# E32_Lora_T20S868MHz.net
KiCad netlist of a schematic drawn in Altium Designer
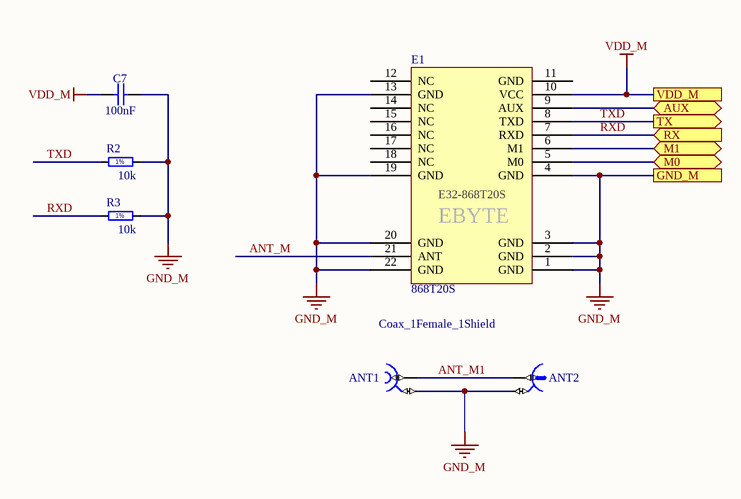
[diagram p0: E32_Lora_T20S868MHz.SchDoc]

(export (version "E")
  (design (tool "Eeschema 10.0.6"))
  (components
    (comp (ref "ANT1")
      (value "Coax_1Female_1Shield")
      (footprint "HUBER-SUHNER_85 SMA-50-0-101/111 NE")
      (fields
        (field (name "PART NUMBER") "HUBER-SUHNER_85_SMA-50-0-101/111_NE")
        (field (name "MANUFACTURER") "HUBER+SUHNER")
        (field (name "MANUFACTURER PART NUMBER") "85_SMA-50-0-101/111_NE")
        (field (name "AUTHOR") "CERN DEM JLC")
      )
      (libsource (lib "Connectors") (part "Coax_1Female_1Shield"))
    )
    (comp (ref "ANT2")
      (value "U.FL")
      (footprint "HIROSE_U.FL-R-SMT-1(10)")
      (fields
        (field (name "PART NUMBER") "HIROSE_U.FL-R-SMT-1(10)")
        (field (name "MANUFACTURER") "HIROSE (HRS)")
        (field (name "MANUFACTURER PART NUMBER") "U.FL-R-SMT-1(10)")
        (field (name "AUTHOR") "CERN DEM JLC")
      )
      (libsource (lib "Connectors") (part "Coax_1Male_1Shield"))
    )
    (comp (ref "C7")
      (value "100nF")
      (footprint "CAPC1608X87N")
      (description "Non-polarised capacitor")
      (fields
        (field (name "PART NUMBER") "CC0603_100NF_50V_10%_X7R")
        (field (name "VOLTAGE") "50V")
        (field (name "AUTHOR") "CERN DEM JLC")
      )
      (libsource (lib "Capacitors") (part "Capacitor - non polarized"))
    )
    (comp (ref "E1")
      (value "868T20S")
      (footprint "E32-T20S")
      (description "Lora Ebyte E32-T30S Module")
      (libsource (lib "alib_pnphien") (part "E32-868T20S"))
    )
    (comp (ref "R2")
      (value "10k")
      (footprint "RESC1608X55N")
      (description "Resistor - 1%")
      (fields
        (field (name "PART NUMBER") "R0603_10K_1%_0.1W_100PPM")
        (field (name "POWER") "0.1W")
        (field (name "AUTHOR") "CERN DEM JLC")
      )
      (libsource (lib "Resistors") (part "Resistor - 1%"))
    )
    (comp (ref "R3")
      (value "10k")
      (footprint "RESC1608X55N")
      (description "Resistor - 1%")
      (fields
        (field (name "PART NUMBER") "R0603_10K_1%_0.1W_100PPM")
        (field (name "POWER") "0.1W")
        (field (name "AUTHOR") "CERN DEM JLC")
      )
      (libsource (lib "Resistors") (part "Resistor - 1%"))
    )
  )
  (nets
    (net (code "1") (name "/ANT_M") (class "Default")
      (node (ref "E1") (pin "21") (pinfunction "ANT_21") (pintype "passive"))
    )
    (net (code "2") (name "/ANT_M1") (class "Default")
      (node (ref "ANT1") (pin "1") (pinfunction "1_1") (pintype "bidirectional"))
      (node (ref "ANT2") (pin "1") (pinfunction "1_1") (pintype "bidirectional"))
    )
    (net (code "3") (name "/AUX") (class "Default")
      (node (ref "E1") (pin "9") (pinfunction "AUX_9") (pintype "passive"))
    )
    (net (code "4") (name "/M0") (class "Default")
      (node (ref "E1") (pin "5") (pinfunction "M0_5") (pintype "passive"))
    )
    (net (code "5") (name "/M1") (class "Default")
      (node (ref "E1") (pin "6") (pinfunction "M1_6") (pintype "passive"))
    )
    (net (code "6") (name "/RXD") (class "Default")
      (node (ref "E1") (pin "7") (pinfunction "RXD_7") (pintype "passive"))
      (node (ref "R3") (pin "1") (pinfunction "1_1") (pintype "passive"))
    )
    (net (code "7") (name "/TXD") (class "Default")
      (node (ref "E1") (pin "8") (pinfunction "TXD_8") (pintype "passive"))
      (node (ref "R2") (pin "1") (pinfunction "1_1") (pintype "passive"))
    )
    (net (code "8") (name "GND_M") (class "Default")
      (node (ref "ANT1") (pin "2") (pinfunction "2_2") (pintype "bidirectional"))
      (node (ref "ANT2") (pin "2") (pinfunction "2_2") (pintype "bidirectional"))
      (node (ref "C7") (pin "2") (pinfunction "2_2") (pintype "passive"))
      (node (ref "E1") (pin "1") (pinfunction "GND_1") (pintype "passive"))
      (node (ref "E1") (pin "13") (pinfunction "GND_13") (pintype "passive"))
      (node (ref "E1") (pin "19") (pinfunction "GND_19") (pintype "passive"))
      (node (ref "E1") (pin "2") (pinfunction "GND_2") (pintype "passive"))
      (node (ref "E1") (pin "20") (pinfunction "GND_20") (pintype "passive"))
      (node (ref "E1") (pin "22") (pinfunction "GND_22") (pintype "passive"))
      (node (ref "E1") (pin "3") (pinfunction "GND_3") (pintype "passive"))
      (node (ref "E1") (pin "4") (pinfunction "GND_4") (pintype "passive"))
      (node (ref "R2") (pin "2") (pinfunction "2_2") (pintype "passive"))
      (node (ref "R3") (pin "2") (pinfunction "2_2") (pintype "passive"))
    )
    (net (code "9") (name "VDD_M") (class "Default")
      (node (ref "C7") (pin "1") (pinfunction "1_1") (pintype "passive"))
      (node (ref "E1") (pin "10") (pinfunction "VCC_10") (pintype "passive"))
    )
    (net (code "10") (name "unconnected-(E1-GND-Pad11)") (class "Default")
      (node (ref "E1") (pin "11") (pinfunction "GND_11") (pintype "passive"))
    )
    (net (code "11") (name "unconnected-(E1-NC-Pad12)") (class "Default")
      (node (ref "E1") (pin "12") (pinfunction "NC_12") (pintype "passive"))
    )
    (net (code "12") (name "unconnected-(E1-NC-Pad14)") (class "Default")
      (node (ref "E1") (pin "14") (pinfunction "NC_14") (pintype "passive"))
    )
    (net (code "13") (name "unconnected-(E1-NC-Pad15)") (class "Default")
      (node (ref "E1") (pin "15") (pinfunction "NC_15") (pintype "passive"))
    )
    (net (code "14") (name "unconnected-(E1-NC-Pad16)") (class "Default")
      (node (ref "E1") (pin "16") (pinfunction "NC_16") (pintype "passive"))
    )
    (net (code "15") (name "unconnected-(E1-NC-Pad17)") (class "Default")
      (node (ref "E1") (pin "17") (pinfunction "NC_17") (pintype "passive"))
    )
    (net (code "16") (name "unconnected-(E1-NC-Pad18)") (class "Default")
      (node (ref "E1") (pin "18") (pinfunction "NC_18") (pintype "passive"))
    )
  )
)
